# SCH_Hydrophonics_system.net
KiCad netlist of a schematic drawn in EasyEDA
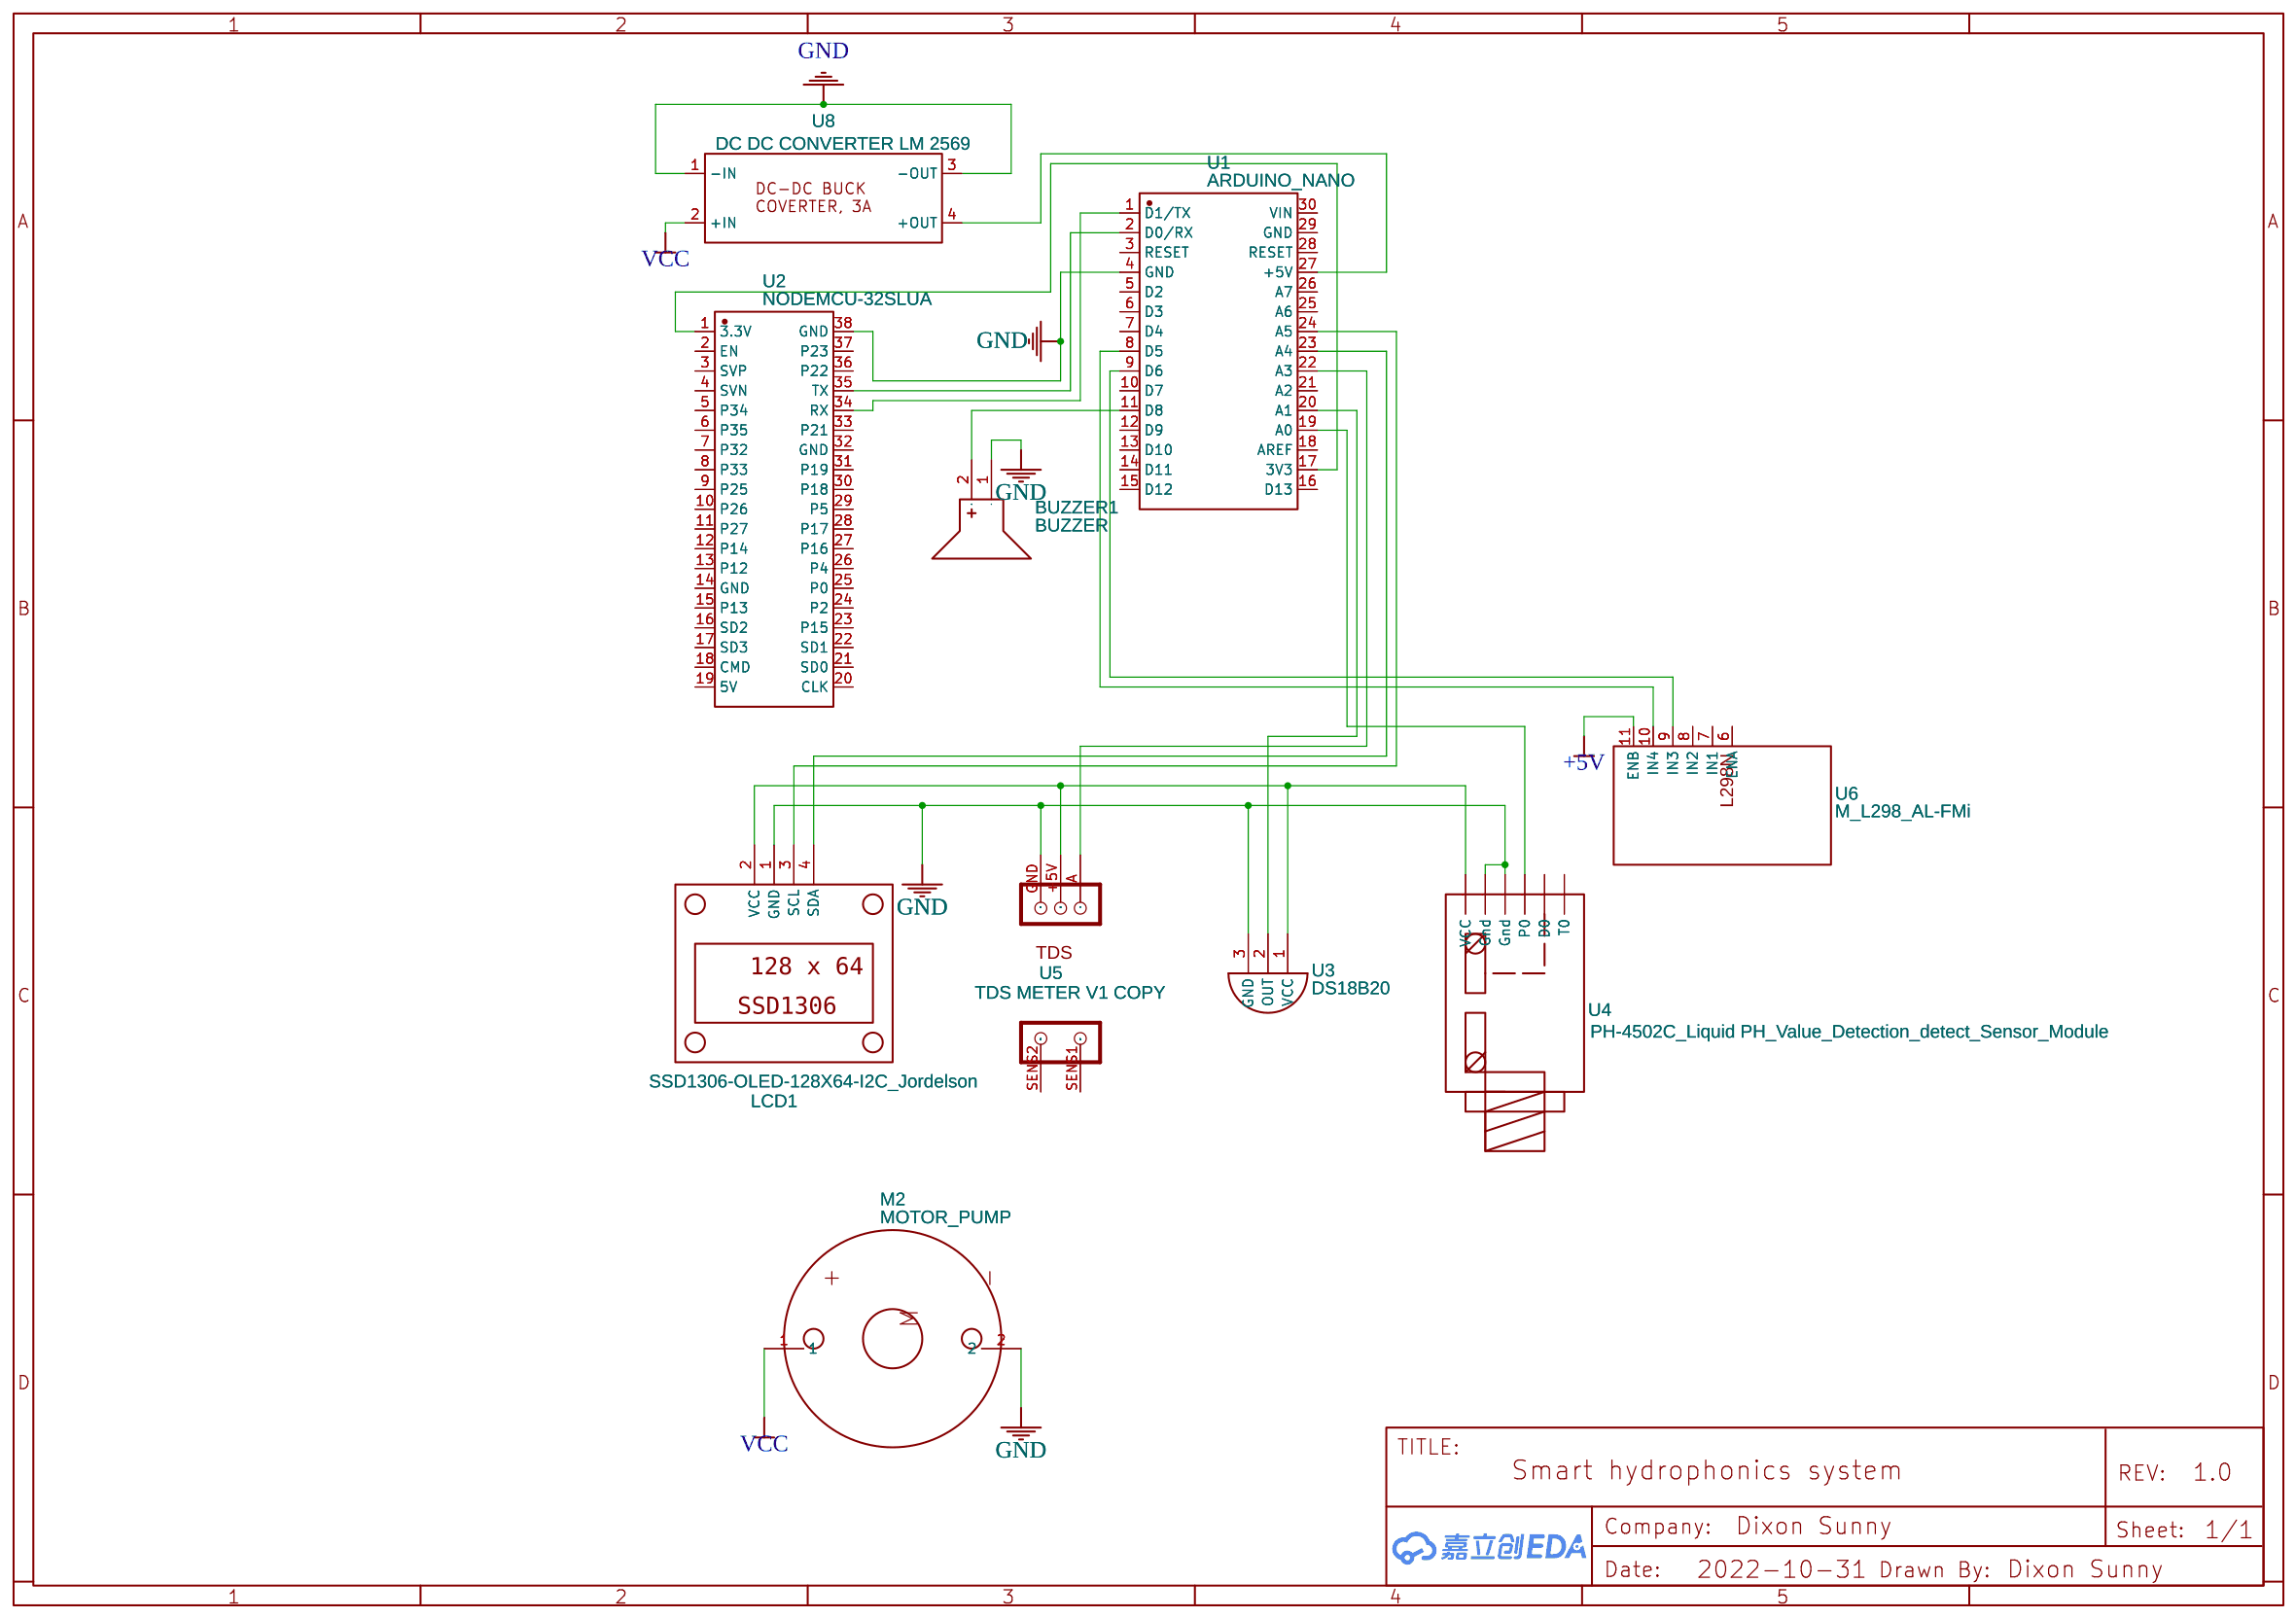
[diagram p0: schematic sheet]

(export (version "E")
  (design (tool "Eeschema 10.0.6"))
  (components
    (comp (ref "BUZZER1")
      (value "BUZZER")
      (fields (field (name "Manufacturer Part") "buzzer"))
      (libsource (lib "") (part "BUZZER"))
    )
    (comp (ref "LCD1")
      (value "SSD1306-OLED-128X64-I2C_Jordelson")
      (libsource (lib "") (part "SSD1306-OLED-128X64-I2C_Jordelson"))
    )
    (comp (ref "M2") (value "MOTOR_PUMP") (libsource (lib "") (part "MOTOR_PUMP")))
    (comp (ref "U1") (value "ARDUINO_NANO") (libsource (lib "") (part "ARDUINO_NANO")))
    (comp (ref "U2")
      (value "NODEMCU-32SLUA")
      (fields
        (field (name "Manufacturer Part") "NodeMCU-32SLua")
        (field (name "Manufacturer") "Ai-Thinker(安信可)")
      )
      (libsource (lib "") (part "NODEMCU-32SLUA"))
    )
    (comp (ref "U3")
      (value "DS18B20")
      (fields (field (name "Manufacturer Part") "New SchematicLib"))
      (libsource (lib "") (part "DS18B20"))
    )
    (comp (ref "U4")
      (value "PH-4502C_Liquid PH_Value_Detection_detect_Sensor_Module")
      (libsource (lib "") (part "PH-4502C_Liquid PH_Value_Detection_detect_Sensor_Module"))
    )
    (comp (ref "U5") (value "TDS METER V1 COPY") (libsource (lib "") (part "TDS METER V1 COPY")))
    (comp (ref "U6") (value "M_L298_AL-FMi") (libsource (lib "") (part "M_L298_AL-FMi")))
    (comp (ref "U8")
      (value "DC DC CONVERTER LM 2569")
      (fields (field (name "Manufacturer Part") "A"))
      (libsource (lib "") (part "DC DC CONVERTER LM 2569"))
    )
  )
  (nets
    (net (code "1") (name "+5V") (class "Default")
      (node (ref "U6") (pin "11") (pinfunction "ENB_11") (pintype "unspecified"))
    )
    (net (code "2") (name "GND") (class "Default")
      (node (ref "BUZZER1") (pin "1") (pinfunction "-_1") (pintype "unspecified"))
      (node (ref "LCD1") (pin "1") (pinfunction "GND_1") (pintype "unspecified"))
      (node (ref "M2") (pin "2") (pinfunction "2_2") (pintype "unspecified"))
      (node (ref "U1") (pin "4") (pinfunction "GND_4") (pintype "unspecified"))
      (node (ref "U2") (pin "38") (pinfunction "GND_38") (pintype "unspecified"))
      (node (ref "U3") (pin "3") (pinfunction "GND_3") (pintype "unspecified"))
      (node (ref "U4") (pin "4") (pinfunction "Gnd_4") (pintype "output"))
      (node (ref "U4") (pin "5") (pinfunction "Gnd_5") (pintype "passive"))
      (node (ref "U5") (pin "GND") (pinfunction "GND_GND") (pintype "passive"))
      (node (ref "U8") (pin "1") (pinfunction "-IN_1") (pintype "unspecified"))
      (node (ref "U8") (pin "3") (pinfunction "-OUT_3") (pintype "unspecified"))
    )
    (net (code "3") (name "Net-(BUZZER1-+)") (class "Default")
      (node (ref "BUZZER1") (pin "2") (pinfunction "+_2") (pintype "unspecified"))
      (node (ref "U1") (pin "11") (pinfunction "D8_11") (pintype "unspecified"))
    )
    (net (code "4") (name "Net-(LCD1-SCL)") (class "Default")
      (node (ref "LCD1") (pin "3") (pinfunction "SCL_3") (pintype "unspecified"))
      (node (ref "U1") (pin "24") (pinfunction "A5_24") (pintype "unspecified"))
    )
    (net (code "5") (name "Net-(LCD1-SDA)") (class "Default")
      (node (ref "LCD1") (pin "4") (pinfunction "SDA_4") (pintype "unspecified"))
      (node (ref "U1") (pin "23") (pinfunction "A4_23") (pintype "unspecified"))
    )
    (net (code "6") (name "Net-(LCD1-VCC)") (class "Default")
      (node (ref "LCD1") (pin "2") (pinfunction "VCC_2") (pintype "unspecified"))
      (node (ref "U3") (pin "1") (pinfunction "VCC_1") (pintype "unspecified"))
      (node (ref "U4") (pin "6") (pinfunction "VCC_6") (pintype "passive"))
      (node (ref "U5") (pin "+5V") (pinfunction "+5V_+5V") (pintype "passive"))
    )
    (net (code "7") (name "Net-(U1-+5V)") (class "Default")
      (node (ref "U1") (pin "27") (pinfunction "+5V_27") (pintype "unspecified"))
      (node (ref "U8") (pin "4") (pinfunction "+OUT_4") (pintype "unspecified"))
    )
    (net (code "8") (name "Net-(U1-3V3)") (class "Default")
      (node (ref "U1") (pin "17") (pinfunction "3V3_17") (pintype "unspecified"))
      (node (ref "U2") (pin "1") (pinfunction "3.3V_1") (pintype "unspecified"))
    )
    (net (code "9") (name "Net-(U1-A0)") (class "Default")
      (node (ref "U1") (pin "19") (pinfunction "A0_19") (pintype "unspecified"))
      (node (ref "U4") (pin "3") (pinfunction "P0_3") (pintype "output"))
    )
    (net (code "10") (name "Net-(U1-A1)") (class "Default")
      (node (ref "U1") (pin "20") (pinfunction "A1_20") (pintype "unspecified"))
      (node (ref "U3") (pin "2") (pinfunction "OUT_2") (pintype "unspecified"))
    )
    (net (code "11") (name "Net-(U1-A3)") (class "Default")
      (node (ref "U1") (pin "22") (pinfunction "A3_22") (pintype "unspecified"))
      (node (ref "U5") (pin "A") (pinfunction "A_A") (pintype "unspecified"))
    )
    (net (code "12") (name "Net-(U1-D0{slash}RX)") (class "Default")
      (node (ref "U1") (pin "2") (pinfunction "D0/RX_2") (pintype "unspecified"))
      (node (ref "U2") (pin "35") (pinfunction "TX_35") (pintype "unspecified"))
    )
    (net (code "13") (name "Net-(U1-D1{slash}TX)") (class "Default")
      (node (ref "U1") (pin "1") (pinfunction "D1/TX_1") (pintype "unspecified"))
      (node (ref "U2") (pin "34") (pinfunction "RX_34") (pintype "unspecified"))
    )
    (net (code "14") (name "Net-(U1-D5)") (class "Default")
      (node (ref "U1") (pin "8") (pinfunction "D5_8") (pintype "unspecified"))
      (node (ref "U6") (pin "10") (pinfunction "IN4_10") (pintype "unspecified"))
    )
    (net (code "15") (name "Net-(U1-D6)") (class "Default")
      (node (ref "U1") (pin "9") (pinfunction "D6_9") (pintype "unspecified"))
      (node (ref "U6") (pin "9") (pinfunction "IN3_9") (pintype "unspecified"))
    )
    (net (code "16") (name "VCC") (class "Default")
      (node (ref "M2") (pin "1") (pinfunction "1_1") (pintype "unspecified"))
      (node (ref "U8") (pin "2") (pinfunction "+IN_2") (pintype "unspecified"))
    )
    (net (code "17") (name "unconnected-(U1-A2-Pad21)") (class "Default")
      (node (ref "U1") (pin "21") (pinfunction "A2_21") (pintype "unspecified"))
    )
    (net (code "18") (name "unconnected-(U1-A6-Pad25)") (class "Default")
      (node (ref "U1") (pin "25") (pinfunction "A6_25") (pintype "unspecified"))
    )
    (net (code "19") (name "unconnected-(U1-A7-Pad26)") (class "Default")
      (node (ref "U1") (pin "26") (pinfunction "A7_26") (pintype "unspecified"))
    )
    (net (code "20") (name "unconnected-(U1-AREF-Pad18)") (class "Default")
      (node (ref "U1") (pin "18") (pinfunction "AREF_18") (pintype "unspecified"))
    )
    (net (code "21") (name "unconnected-(U1-D2-Pad5)") (class "Default")
      (node (ref "U1") (pin "5") (pinfunction "D2_5") (pintype "unspecified"))
    )
    (net (code "22") (name "unconnected-(U1-D3-Pad6)") (class "Default")
      (node (ref "U1") (pin "6") (pinfunction "D3_6") (pintype "unspecified"))
    )
    (net (code "23") (name "unconnected-(U1-D4-Pad7)") (class "Default")
      (node (ref "U1") (pin "7") (pinfunction "D4_7") (pintype "unspecified"))
    )
    (net (code "24") (name "unconnected-(U1-D7-Pad10)") (class "Default")
      (node (ref "U1") (pin "10") (pinfunction "D7_10") (pintype "unspecified"))
    )
    (net (code "25") (name "unconnected-(U1-D9-Pad12)") (class "Default")
      (node (ref "U1") (pin "12") (pinfunction "D9_12") (pintype "unspecified"))
    )
    (net (code "26") (name "unconnected-(U1-D10-Pad13)") (class "Default")
      (node (ref "U1") (pin "13") (pinfunction "D10_13") (pintype "unspecified"))
    )
    (net (code "27") (name "unconnected-(U1-D11-Pad14)") (class "Default")
      (node (ref "U1") (pin "14") (pinfunction "D11_14") (pintype "unspecified"))
    )
    (net (code "28") (name "unconnected-(U1-D12-Pad15)") (class "Default")
      (node (ref "U1") (pin "15") (pinfunction "D12_15") (pintype "unspecified"))
    )
    (net (code "29") (name "unconnected-(U1-D13-Pad16)") (class "Default")
      (node (ref "U1") (pin "16") (pinfunction "D13_16") (pintype "unspecified"))
    )
    (net (code "30") (name "unconnected-(U1-GND-Pad29)") (class "Default")
      (node (ref "U1") (pin "29") (pinfunction "GND_29") (pintype "unspecified"))
    )
    (net (code "31") (name "unconnected-(U1-RESET-Pad3)") (class "Default")
      (node (ref "U1") (pin "3") (pinfunction "RESET_3") (pintype "unspecified"))
    )
    (net (code "32") (name "unconnected-(U1-RESET-Pad28)") (class "Default")
      (node (ref "U1") (pin "28") (pinfunction "RESET_28") (pintype "unspecified"))
    )
    (net (code "33") (name "unconnected-(U1-VIN-Pad30)") (class "Default")
      (node (ref "U1") (pin "30") (pinfunction "VIN_30") (pintype "unspecified"))
    )
    (net (code "34") (name "unconnected-(U2-5V-Pad19)") (class "Default")
      (node (ref "U2") (pin "19") (pinfunction "5V_19") (pintype "unspecified"))
    )
    (net (code "35") (name "unconnected-(U2-CLK-Pad20)") (class "Default")
      (node (ref "U2") (pin "20") (pinfunction "CLK_20") (pintype "unspecified"))
    )
    (net (code "36") (name "unconnected-(U2-CMD-Pad18)") (class "Default")
      (node (ref "U2") (pin "18") (pinfunction "CMD_18") (pintype "unspecified"))
    )
    (net (code "37") (name "unconnected-(U2-EN-Pad2)") (class "Default")
      (node (ref "U2") (pin "2") (pinfunction "EN_2") (pintype "unspecified"))
    )
    (net (code "38") (name "unconnected-(U2-GND-Pad14)") (class "Default")
      (node (ref "U2") (pin "14") (pinfunction "GND_14") (pintype "unspecified"))
    )
    (net (code "39") (name "unconnected-(U2-GND-Pad32)") (class "Default")
      (node (ref "U2") (pin "32") (pinfunction "GND_32") (pintype "unspecified"))
    )
    (net (code "40") (name "unconnected-(U2-P0-Pad25)") (class "Default")
      (node (ref "U2") (pin "25") (pinfunction "P0_25") (pintype "unspecified"))
    )
    (net (code "41") (name "unconnected-(U2-P2-Pad24)") (class "Default")
      (node (ref "U2") (pin "24") (pinfunction "P2_24") (pintype "unspecified"))
    )
    (net (code "42") (name "unconnected-(U2-P4-Pad26)") (class "Default")
      (node (ref "U2") (pin "26") (pinfunction "P4_26") (pintype "unspecified"))
    )
    (net (code "43") (name "unconnected-(U2-P5-Pad29)") (class "Default")
      (node (ref "U2") (pin "29") (pinfunction "P5_29") (pintype "unspecified"))
    )
    (net (code "44") (name "unconnected-(U2-P12-Pad13)") (class "Default")
      (node (ref "U2") (pin "13") (pinfunction "P12_13") (pintype "unspecified"))
    )
    (net (code "45") (name "unconnected-(U2-P13-Pad15)") (class "Default")
      (node (ref "U2") (pin "15") (pinfunction "P13_15") (pintype "unspecified"))
    )
    (net (code "46") (name "unconnected-(U2-P14-Pad12)") (class "Default")
      (node (ref "U2") (pin "12") (pinfunction "P14_12") (pintype "unspecified"))
    )
    (net (code "47") (name "unconnected-(U2-P15-Pad23)") (class "Default")
      (node (ref "U2") (pin "23") (pinfunction "P15_23") (pintype "unspecified"))
    )
    (net (code "48") (name "unconnected-(U2-P16-Pad27)") (class "Default")
      (node (ref "U2") (pin "27") (pinfunction "P16_27") (pintype "unspecified"))
    )
    (net (code "49") (name "unconnected-(U2-P17-Pad28)") (class "Default")
      (node (ref "U2") (pin "28") (pinfunction "P17_28") (pintype "unspecified"))
    )
    (net (code "50") (name "unconnected-(U2-P18-Pad30)") (class "Default")
      (node (ref "U2") (pin "30") (pinfunction "P18_30") (pintype "unspecified"))
    )
    (net (code "51") (name "unconnected-(U2-P19-Pad31)") (class "Default")
      (node (ref "U2") (pin "31") (pinfunction "P19_31") (pintype "unspecified"))
    )
    (net (code "52") (name "unconnected-(U2-P21-Pad33)") (class "Default")
      (node (ref "U2") (pin "33") (pinfunction "P21_33") (pintype "unspecified"))
    )
    (net (code "53") (name "unconnected-(U2-P22-Pad36)") (class "Default")
      (node (ref "U2") (pin "36") (pinfunction "P22_36") (pintype "unspecified"))
    )
    (net (code "54") (name "unconnected-(U2-P23-Pad37)") (class "Default")
      (node (ref "U2") (pin "37") (pinfunction "P23_37") (pintype "unspecified"))
    )
    (net (code "55") (name "unconnected-(U2-P25-Pad9)") (class "Default")
      (node (ref "U2") (pin "9") (pinfunction "P25_9") (pintype "unspecified"))
    )
    (net (code "56") (name "unconnected-(U2-P26-Pad10)") (class "Default")
      (node (ref "U2") (pin "10") (pinfunction "P26_10") (pintype "unspecified"))
    )
    (net (code "57") (name "unconnected-(U2-P27-Pad11)") (class "Default")
      (node (ref "U2") (pin "11") (pinfunction "P27_11") (pintype "unspecified"))
    )
    (net (code "58") (name "unconnected-(U2-P32-Pad7)") (class "Default")
      (node (ref "U2") (pin "7") (pinfunction "P32_7") (pintype "unspecified"))
    )
    (net (code "59") (name "unconnected-(U2-P33-Pad8)") (class "Default")
      (node (ref "U2") (pin "8") (pinfunction "P33_8") (pintype "unspecified"))
    )
    (net (code "60") (name "unconnected-(U2-P34-Pad5)") (class "Default")
      (node (ref "U2") (pin "5") (pinfunction "P34_5") (pintype "unspecified"))
    )
    (net (code "61") (name "unconnected-(U2-P35-Pad6)") (class "Default")
      (node (ref "U2") (pin "6") (pinfunction "P35_6") (pintype "unspecified"))
    )
    (net (code "62") (name "unconnected-(U2-SD0-Pad21)") (class "Default")
      (node (ref "U2") (pin "21") (pinfunction "SD0_21") (pintype "unspecified"))
    )
    (net (code "63") (name "unconnected-(U2-SD1-Pad22)") (class "Default")
      (node (ref "U2") (pin "22") (pinfunction "SD1_22") (pintype "unspecified"))
    )
    (net (code "64") (name "unconnected-(U2-SD2-Pad16)") (class "Default")
      (node (ref "U2") (pin "16") (pinfunction "SD2_16") (pintype "unspecified"))
    )
    (net (code "65") (name "unconnected-(U2-SD3-Pad17)") (class "Default")
      (node (ref "U2") (pin "17") (pinfunction "SD3_17") (pintype "unspecified"))
    )
    (net (code "66") (name "unconnected-(U2-SVN-Pad4)") (class "Default")
      (node (ref "U2") (pin "4") (pinfunction "SVN_4") (pintype "unspecified"))
    )
    (net (code "67") (name "unconnected-(U2-SVP-Pad3)") (class "Default")
      (node (ref "U2") (pin "3") (pinfunction "SVP_3") (pintype "unspecified"))
    )
    (net (code "68") (name "unconnected-(U4-D0-Pad2)") (class "Default")
      (node (ref "U4") (pin "2") (pinfunction "D0_2") (pintype "output"))
    )
    (net (code "69") (name "unconnected-(U4-T0-Pad1)") (class "Default")
      (node (ref "U4") (pin "1") (pinfunction "T0_1") (pintype "output"))
    )
    (net (code "70") (name "unconnected-(U5-PadSENS1)") (class "Default")
      (node (ref "U5") (pin "SENS1") (pinfunction "SENS1_SENS1") (pintype "passive"))
    )
    (net (code "71") (name "unconnected-(U5-PadSENS2)") (class "Default")
      (node (ref "U5") (pin "SENS2") (pinfunction "SENS2_SENS2") (pintype "unspecified"))
    )
    (net (code "72") (name "unconnected-(U6-ENA-Pad6)") (class "Default")
      (node (ref "U6") (pin "6") (pinfunction "ENA_6") (pintype "unspecified"))
    )
    (net (code "73") (name "unconnected-(U6-IN1-Pad7)") (class "Default")
      (node (ref "U6") (pin "7") (pinfunction "IN1_7") (pintype "unspecified"))
    )
    (net (code "74") (name "unconnected-(U6-IN2-Pad8)") (class "Default")
      (node (ref "U6") (pin "8") (pinfunction "IN2_8") (pintype "unspecified"))
    )
  )
)
